# schematic.net
KiCad netlist of a schematic drawn in EasyEDA
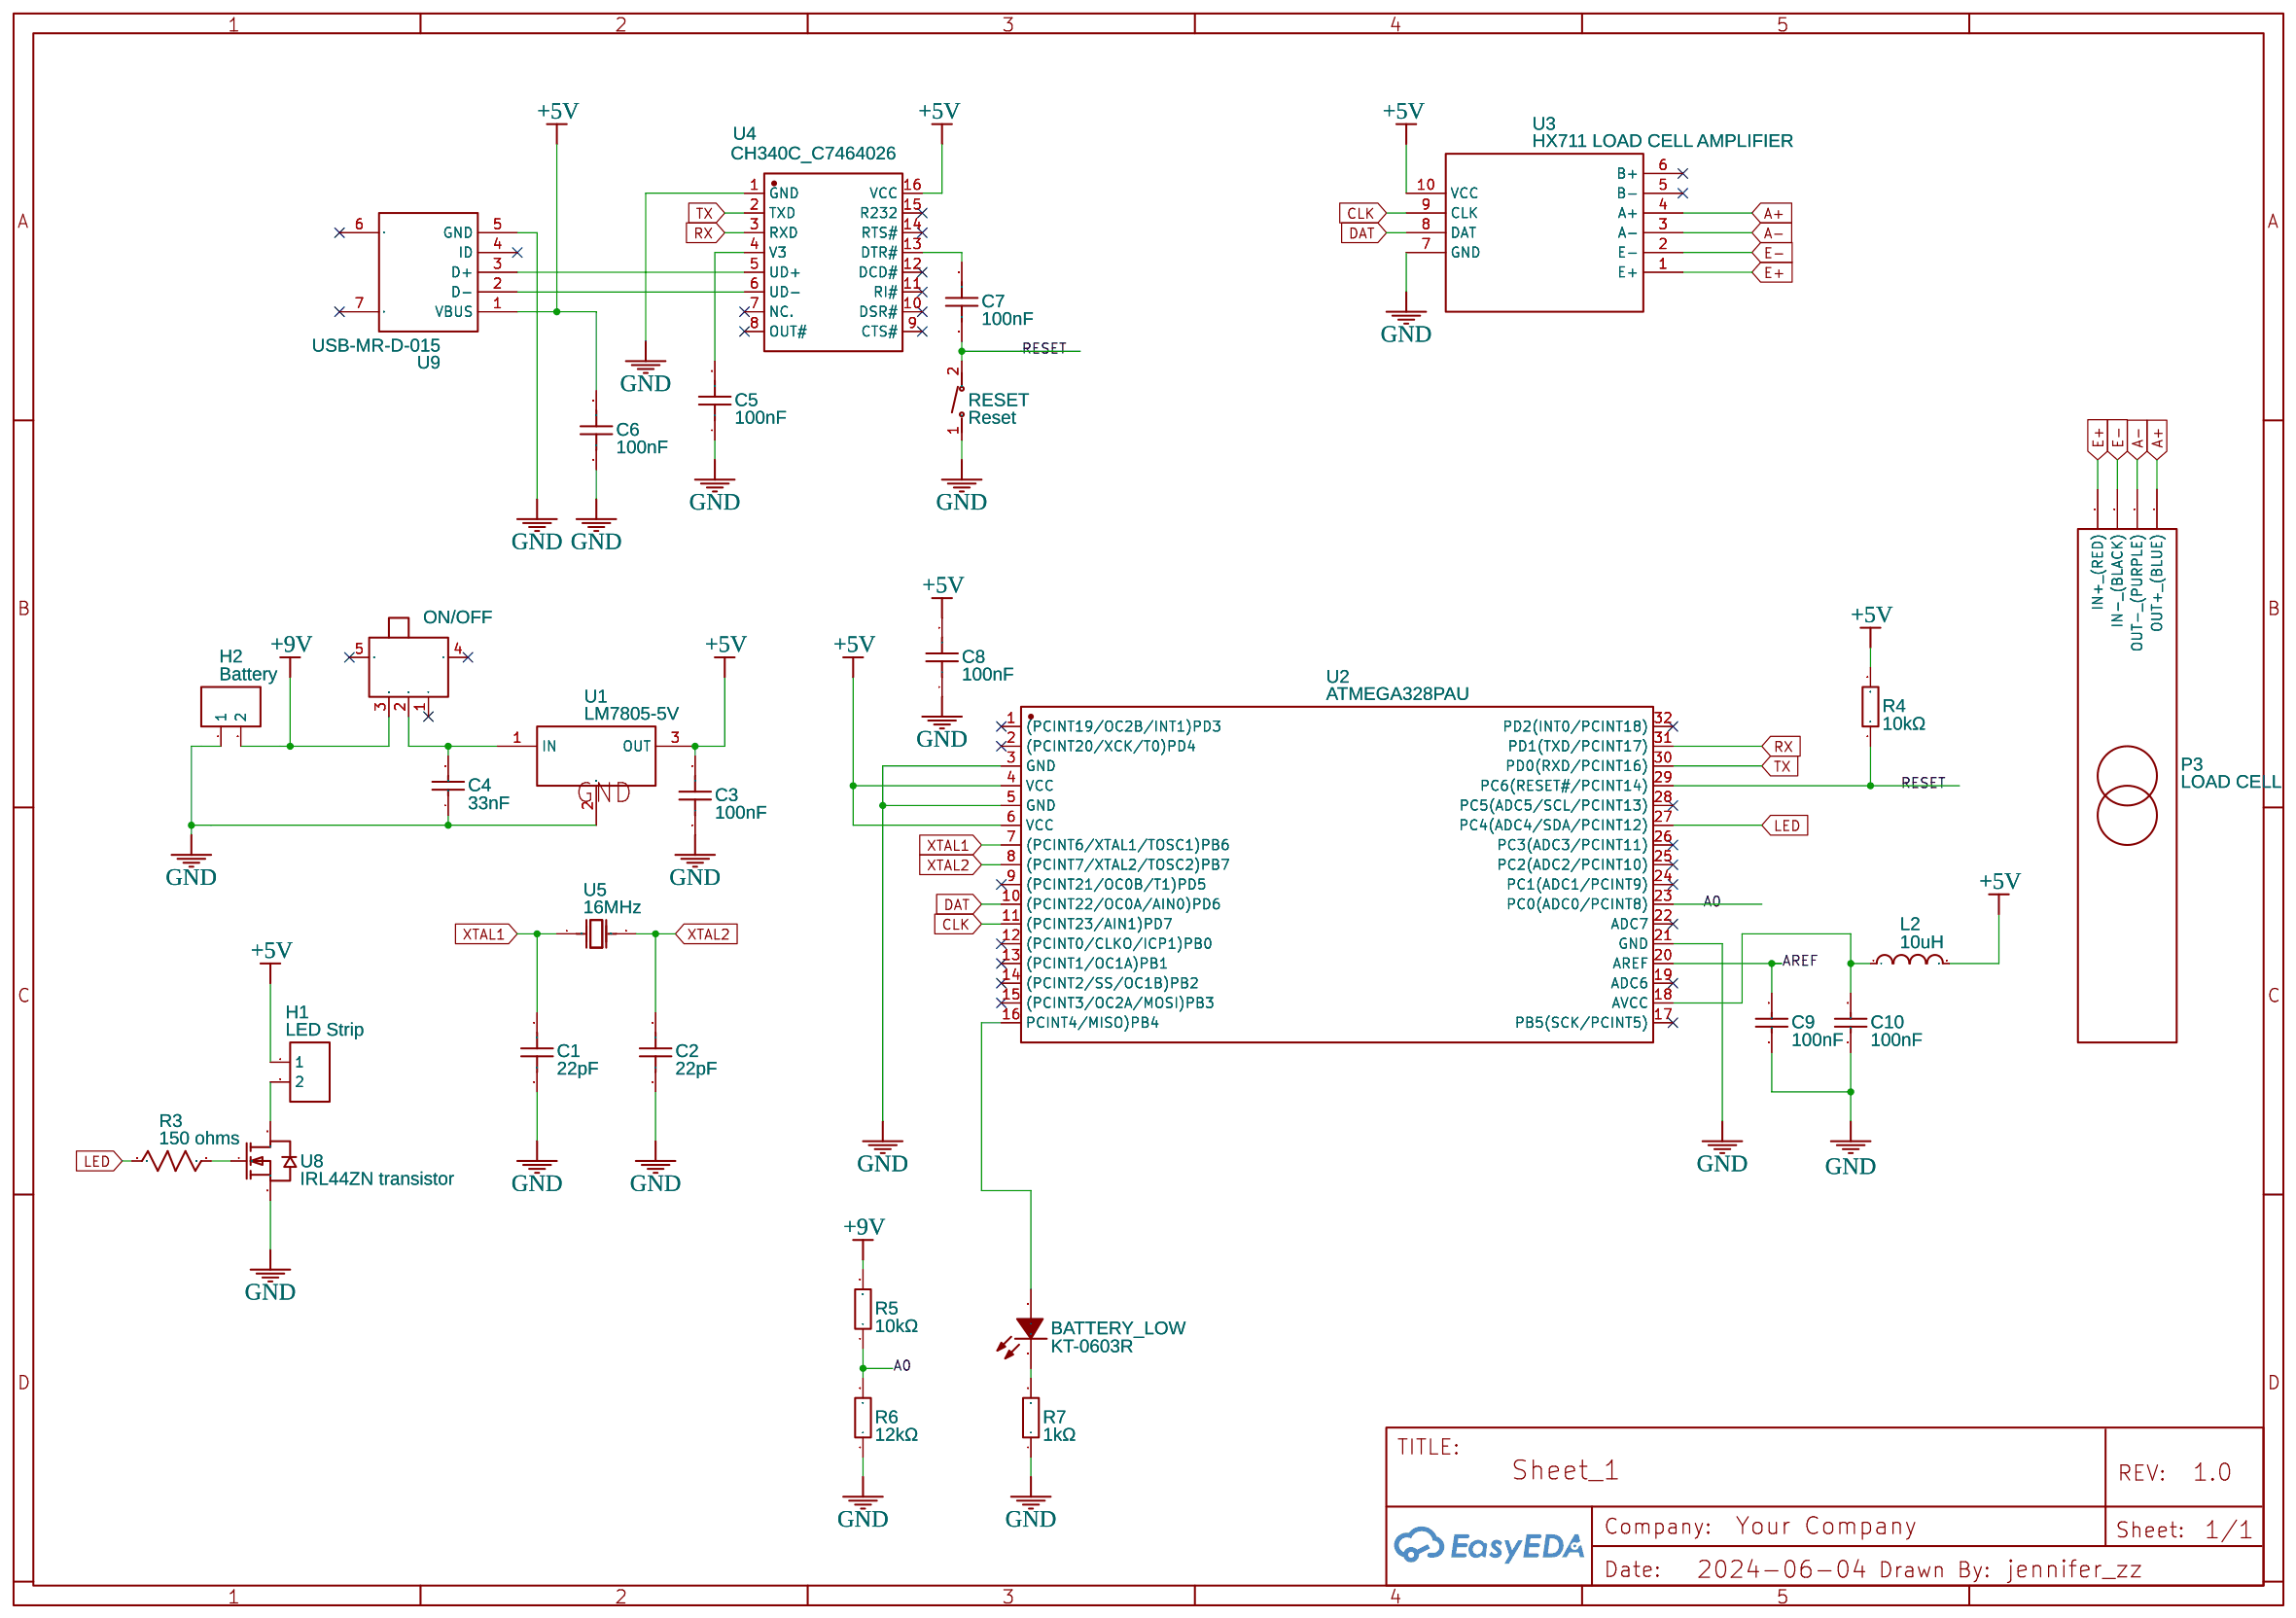
[diagram p0: schematic sheet]

(export (version "E")
  (design (tool "Eeschema 10.0.6"))
  (components
    (comp (ref "BATTERY_LOW")
      (value "KT-0603R")
      (fields (field (name "Manufacturer") "KENTO"))
      (libsource (lib "") (part "KT-0603R"))
    )
    (comp (ref "C1") (value "22pF") (libsource (lib "") (part "C_0603_US")))
    (comp (ref "C2") (value "22pF") (libsource (lib "") (part "C_0603_US")))
    (comp (ref "C3")
      (value "100nF")
      (fields
        (field (name "Manufacturer Part") "CC0603KRX7R9BB104")
        (field (name "Manufacturer") "YAGEO(国巨)")
      )
      (libsource (lib "") (part "CC0603KRX7R9BB104"))
    )
    (comp (ref "C4")
      (value "33nF")
      (fields
        (field (name "Manufacturer Part") "CL10B333KB8NNNC")
        (field (name "Manufacturer") "SAMSUNG(三星)")
      )
      (libsource (lib "") (part "CL10B333KB8NNNC"))
    )
    (comp (ref "C5")
      (value "100nF")
      (fields
        (field (name "Manufacturer Part") "CC0603KRX7R9BB104")
        (field (name "Manufacturer") "YAGEO(国巨)")
      )
      (libsource (lib "") (part "CC0603KRX7R9BB104"))
    )
    (comp (ref "C6")
      (value "100nF")
      (fields
        (field (name "Manufacturer Part") "CC0603KRX7R9BB104")
        (field (name "Manufacturer") "YAGEO(国巨)")
      )
      (libsource (lib "") (part "CC0603KRX7R9BB104"))
    )
    (comp (ref "C7")
      (value "100nF")
      (fields
        (field (name "Manufacturer Part") "CC0603KRX7R9BB104")
        (field (name "Manufacturer") "YAGEO(国巨)")
      )
      (libsource (lib "") (part "CC0603KRX7R9BB104"))
    )
    (comp (ref "C8")
      (value "100nF")
      (fields
        (field (name "Manufacturer Part") "CC0603KRX7R9BB104")
        (field (name "Manufacturer") "YAGEO(国巨)")
      )
      (libsource (lib "") (part "CC0603KRX7R9BB104"))
    )
    (comp (ref "C9")
      (value "100nF")
      (fields
        (field (name "Manufacturer Part") "CL10B104KO8NNNC")
        (field (name "Manufacturer") "SAMSUNG(三星)")
      )
      (libsource (lib "") (part "CL10B104KO8NNNC"))
    )
    (comp (ref "C10")
      (value "100nF")
      (fields
        (field (name "Manufacturer Part") "CL10B104KO8NNNC")
        (field (name "Manufacturer") "SAMSUNG(三星)")
      )
      (libsource (lib "") (part "CL10B104KO8NNNC"))
    )
    (comp (ref "H1") (value "LED Strip") (libsource (lib "") (part "HDR-F-2.54_1x2_1")))
    (comp (ref "H2") (value "Battery") (libsource (lib "") (part "HDR-F-2.54_1x2")))
    (comp (ref "L2")
      (value "10uH")
      (fields (field (name "Manufacturer Part") "CV201210-100K") (field (name "Manufacturer") "BOURNS"))
      (libsource (lib "") (part "CV201210-100K"))
    )
    (comp (ref "ON/OFF")
      (value "switch")
      (fields
        (field (name "Manufacturer Part") "SS12D07VG4 087")
        (field (name "Manufacturer") "SHOU HAN(首韩)")
      )
      (libsource (lib "") (part "SS12D07VG4 087"))
    )
    (comp (ref "P3") (value "LOAD CELL") (libsource (lib "") (part "LOAD CELL")))
    (comp (ref "R3") (value "150 ohms") (libsource (lib "") (part "R_0603_US")))
    (comp (ref "R4")
      (value "10kΩ")
      (fields
        (field (name "Manufacturer Part") "0603WAF1002T5E")
        (field (name "Manufacturer") "UNI-ROYAL(厚声)")
      )
      (libsource (lib "") (part "0603WAF1002T5E"))
    )
    (comp (ref "R5")
      (value "10kΩ")
      (fields
        (field (name "Manufacturer Part") "0603WAF1002T5E")
        (field (name "Manufacturer") "UNI-ROYAL(厚声)")
      )
      (libsource (lib "") (part "0603WAF1002T5E"))
    )
    (comp (ref "R6")
      (value "12kΩ")
      (fields
        (field (name "Manufacturer Part") "QR0603F12K0P05Z")
        (field (name "Manufacturer") "EVER OHMS(天二科技)")
      )
      (libsource (lib "") (part "QR0603F12KP05"))
    )
    (comp (ref "R7")
      (value "1kΩ")
      (fields
        (field (name "Manufacturer Part") "0603WAF1001T5E")
        (field (name "Manufacturer") "UNI-ROYAL(厚声)")
      )
      (libsource (lib "") (part "0603WAF1001T5E"))
    )
    (comp (ref "RESET")
      (value "Reset")
      (fields (field (name "Manufacturer Part") "BUTTON"))
      (libsource (lib "") (part "BUTTON_C9900040040"))
    )
    (comp (ref "U1") (value "LM7805-5V") (libsource (lib "") (part "LM7805-5V")))
    (comp (ref "U2")
      (value "ATMEGA328PAU")
      (fields (field (name "Manufacturer Part") "Atmega328pAU"))
      (libsource (lib "") (part "ATMEGA328PAU"))
    )
    (comp (ref "U3")
      (value "HX711 LOAD CELL AMPLIFIER")
      (libsource (lib "") (part "HX711 LOAD CELL AMPLIFIER"))
    )
    (comp (ref "U4")
      (value "CH340C_C7464026")
      (fields (field (name "Manufacturer Part") "CH340C") (field (name "Manufacturer") "WCH(南京沁恒)"))
      (libsource (lib "") (part "CH340C_C7464026"))
    )
    (comp (ref "U5")
      (value "16MHz")
      (fields (field (name "Manufacturer Part") "D22011000143-Y1"))
      (libsource (lib "") (part "D22011000143-Y1"))
    )
    (comp (ref "U8")
      (value "IRL44ZN transistor")
      (fields (field (name "Manufacturer Part") "si2302-nmosfet"))
      (libsource (lib "") (part "SI2302-NMOSFET"))
    )
    (comp (ref "U9")
      (value "USB-MR-D-015")
      (fields (field (name "Manufacturer") "DEALON(德艺隆)"))
      (libsource (lib "") (part "USB-MR-D-015"))
    )
  )
  (nets
    (net (code "1") (name "+5V") (class "Default")
      (node (ref "C3") (pin "2") (pinfunction "2_2") (pintype "unspecified"))
      (node (ref "C6") (pin "2") (pinfunction "2_2") (pintype "unspecified"))
      (node (ref "C8") (pin "2") (pinfunction "2_2") (pintype "unspecified"))
      (node (ref "H1") (pin "1") (pinfunction "1_1") (pintype "input"))
      (node (ref "L2") (pin "2") (pinfunction "2_2") (pintype "unspecified"))
      (node (ref "R4") (pin "2") (pinfunction "2_2") (pintype "input"))
      (node (ref "U1") (pin "3") (pinfunction "OUT_3") (pintype "passive"))
      (node (ref "U2") (pin "4") (pinfunction "VCC_4") (pintype "unspecified"))
      (node (ref "U2") (pin "6") (pinfunction "VCC_6") (pintype "unspecified"))
      (node (ref "U3") (pin "10") (pinfunction "VCC_10") (pintype "unspecified"))
      (node (ref "U4") (pin "16") (pinfunction "VCC_16") (pintype "unspecified"))
      (node (ref "U9") (pin "1") (pinfunction "VBUS_1") (pintype "unspecified"))
    )
    (net (code "2") (name "+9V") (class "Default")
      (node (ref "H2") (pin "2") (pinfunction "2_2") (pintype "input"))
      (node (ref "ON/OFF") (pin "3") (pinfunction "3_3") (pintype "unspecified"))
      (node (ref "R5") (pin "2") (pinfunction "2_2") (pintype "input"))
    )
    (net (code "3") (name "/A0") (class "Default")
      (node (ref "R5") (pin "1") (pinfunction "1_1") (pintype "input"))
      (node (ref "R6") (pin "2") (pinfunction "2_2") (pintype "unspecified"))
      (node (ref "U2") (pin "23") (pinfunction "PC0(ADC0/PCINT8)_23") (pintype "unspecified"))
    )
    (net (code "4") (name "/AREF") (class "Default")
      (node (ref "C9") (pin "2") (pinfunction "2_2") (pintype "input"))
      (node (ref "U2") (pin "20") (pinfunction "AREF_20") (pintype "unspecified"))
    )
    (net (code "5") (name "/RESET") (class "Default")
      (node (ref "C7") (pin "1") (pinfunction "1_1") (pintype "unspecified"))
      (node (ref "R4") (pin "1") (pinfunction "1_1") (pintype "input"))
      (node (ref "RESET") (pin "2") (pinfunction "B_2") (pintype "unspecified"))
      (node (ref "U2") (pin "29") (pinfunction "PC6(RESET#/PCINT14)_29") (pintype "unspecified"))
    )
    (net (code "6") (name "A+") (class "Default")
      (node (ref "P3") (pin "4") (pinfunction "OUT+_(BLUE)_4") (pintype "unspecified"))
      (node (ref "U3") (pin "4") (pinfunction "A+_4") (pintype "unspecified"))
    )
    (net (code "7") (name "A-") (class "Default")
      (node (ref "P3") (pin "3") (pinfunction "OUT-_(PURPLE)_3") (pintype "unspecified"))
      (node (ref "U3") (pin "3") (pinfunction "A-_3") (pintype "unspecified"))
    )
    (net (code "8") (name "CLK") (class "Default")
      (node (ref "U2") (pin "11") (pinfunction "(PCINT23/AIN1)PD7_11") (pintype "unspecified"))
      (node (ref "U3") (pin "9") (pinfunction "CLK_9") (pintype "unspecified"))
    )
    (net (code "9") (name "DAT") (class "Default")
      (node (ref "U2") (pin "10") (pinfunction "(PCINT22/OC0A/AIN0)PD6_10") (pintype "unspecified"))
      (node (ref "U3") (pin "8") (pinfunction "DAT_8") (pintype "unspecified"))
    )
    (net (code "10") (name "E+") (class "Default")
      (node (ref "P3") (pin "1") (pinfunction "IN+_(RED)_1") (pintype "unspecified"))
      (node (ref "U3") (pin "1") (pinfunction "E+_1") (pintype "unspecified"))
    )
    (net (code "11") (name "E-") (class "Default")
      (node (ref "P3") (pin "2") (pinfunction "IN-_(BLACK)_2") (pintype "unspecified"))
      (node (ref "U3") (pin "2") (pinfunction "E-_2") (pintype "unspecified"))
    )
    (net (code "12") (name "GND") (class "Default")
      (node (ref "C1") (pin "2") (pinfunction "2_2") (pintype "unspecified"))
      (node (ref "C10") (pin "1") (pinfunction "1_1") (pintype "input"))
      (node (ref "C2") (pin "2") (pinfunction "2_2") (pintype "unspecified"))
      (node (ref "C3") (pin "1") (pinfunction "1_1") (pintype "unspecified"))
      (node (ref "C4") (pin "1") (pinfunction "1_1") (pintype "input"))
      (node (ref "C5") (pin "1") (pinfunction "1_1") (pintype "unspecified"))
      (node (ref "C6") (pin "1") (pinfunction "1_1") (pintype "unspecified"))
      (node (ref "C8") (pin "1") (pinfunction "1_1") (pintype "unspecified"))
      (node (ref "C9") (pin "1") (pinfunction "1_1") (pintype "input"))
      (node (ref "H2") (pin "1") (pinfunction "1_1") (pintype "input"))
      (node (ref "R6") (pin "1") (pinfunction "1_1") (pintype "unspecified"))
      (node (ref "R7") (pin "1") (pinfunction "1_1") (pintype "input"))
      (node (ref "RESET") (pin "1") (pinfunction "A_1") (pintype "unspecified"))
      (node (ref "U1") (pin "2") (pinfunction "GND_2") (pintype "passive"))
      (node (ref "U2") (pin "21") (pinfunction "GND_21") (pintype "unspecified"))
      (node (ref "U2") (pin "3") (pinfunction "GND_3") (pintype "unspecified"))
      (node (ref "U2") (pin "5") (pinfunction "GND_5") (pintype "unspecified"))
      (node (ref "U3") (pin "7") (pinfunction "GND_7") (pintype "unspecified"))
      (node (ref "U4") (pin "1") (pinfunction "GND_1") (pintype "unspecified"))
      (node (ref "U8") (pin "2") (pinfunction "S_2") (pintype "unspecified"))
      (node (ref "U9") (pin "5") (pinfunction "GND_5") (pintype "unspecified"))
    )
    (net (code "13") (name "LED") (class "Default")
      (node (ref "R3") (pin "1") (pinfunction "1_1") (pintype "unspecified"))
      (node (ref "U2") (pin "27") (pinfunction "PC4(ADC4/SDA/PCINT12)_27") (pintype "unspecified"))
    )
    (net (code "14") (name "Net-(BATTERY_LOW-A)") (class "Default")
      (node (ref "BATTERY_LOW") (pin "2") (pinfunction "A_2") (pintype "unspecified"))
      (node (ref "U2") (pin "16") (pinfunction "PCINT4/MISO)PB4_16") (pintype "unspecified"))
    )
    (net (code "15") (name "Net-(BATTERY_LOW-K)") (class "Default")
      (node (ref "BATTERY_LOW") (pin "1") (pinfunction "K_1") (pintype "unspecified"))
      (node (ref "R7") (pin "2") (pinfunction "2_2") (pintype "input"))
    )
    (net (code "16") (name "Net-(U1-IN)") (class "Default")
      (node (ref "C4") (pin "2") (pinfunction "2_2") (pintype "input"))
      (node (ref "ON/OFF") (pin "2") (pinfunction "2_2") (pintype "unspecified"))
      (node (ref "U1") (pin "1") (pinfunction "IN_1") (pintype "passive"))
    )
    (net (code "17") (name "Net-(U2-AVCC)") (class "Default")
      (node (ref "C10") (pin "2") (pinfunction "2_2") (pintype "input"))
      (node (ref "L2") (pin "1") (pinfunction "1_1") (pintype "unspecified"))
      (node (ref "U2") (pin "18") (pinfunction "AVCC_18") (pintype "unspecified"))
    )
    (net (code "18") (name "Net-(U4-DTR#)") (class "Default")
      (node (ref "C7") (pin "2") (pinfunction "2_2") (pintype "unspecified"))
      (node (ref "U4") (pin "13") (pinfunction "DTR#_13") (pintype "unspecified"))
    )
    (net (code "19") (name "Net-(U4-UD+)") (class "Default")
      (node (ref "U4") (pin "5") (pinfunction "UD+_5") (pintype "unspecified"))
      (node (ref "U9") (pin "3") (pinfunction "D+_3") (pintype "unspecified"))
    )
    (net (code "20") (name "Net-(U4-UD-)") (class "Default")
      (node (ref "U4") (pin "6") (pinfunction "UD-_6") (pintype "unspecified"))
      (node (ref "U9") (pin "2") (pinfunction "D-_2") (pintype "unspecified"))
    )
    (net (code "21") (name "Net-(U4-V3)") (class "Default")
      (node (ref "C5") (pin "2") (pinfunction "2_2") (pintype "unspecified"))
      (node (ref "U4") (pin "4") (pinfunction "V3_4") (pintype "unspecified"))
    )
    (net (code "22") (name "Net-(U8-D)") (class "Default")
      (node (ref "H1") (pin "2") (pinfunction "2_2") (pintype "input"))
      (node (ref "U8") (pin "3") (pinfunction "D_3") (pintype "unspecified"))
    )
    (net (code "23") (name "Net-(U8-G)") (class "Default")
      (node (ref "R3") (pin "2") (pinfunction "2_2") (pintype "unspecified"))
      (node (ref "U8") (pin "1") (pinfunction "G_1") (pintype "unspecified"))
    )
    (net (code "24") (name "RX") (class "Default")
      (node (ref "U2") (pin "31") (pinfunction "PD1(TXD/PCINT17)_31") (pintype "unspecified"))
      (node (ref "U4") (pin "3") (pinfunction "RXD_3") (pintype "unspecified"))
    )
    (net (code "25") (name "TX") (class "Default")
      (node (ref "U2") (pin "30") (pinfunction "PD0(RXD/PCINT16)_30") (pintype "unspecified"))
      (node (ref "U4") (pin "2") (pinfunction "TXD_2") (pintype "unspecified"))
    )
    (net (code "26") (name "XTAL1") (class "Default")
      (node (ref "C1") (pin "1") (pinfunction "1_1") (pintype "unspecified"))
      (node (ref "U2") (pin "7") (pinfunction "(PCINT6/XTAL1/TOSC1)PB6_7") (pintype "unspecified"))
      (node (ref "U5") (pin "1") (pinfunction "OSC1_1") (pintype "input"))
    )
    (net (code "27") (name "XTAL2") (class "Default")
      (node (ref "C2") (pin "1") (pinfunction "1_1") (pintype "unspecified"))
      (node (ref "U2") (pin "8") (pinfunction "(PCINT7/XTAL2/TOSC2)PB7_8") (pintype "unspecified"))
      (node (ref "U5") (pin "2") (pinfunction "OSC2_2") (pintype "input"))
    )
    (net (code "28") (name "unconnected-(ON/OFF-Pad1)") (class "Default")
      (node (ref "ON/OFF") (pin "1") (pinfunction "1_1") (pintype "unspecified+no_connect"))
    )
    (net (code "29") (name "unconnected-(ON/OFF-Pad4)") (class "Default")
      (node (ref "ON/OFF") (pin "4") (pinfunction "4_4") (pintype "unspecified+no_connect"))
    )
    (net (code "30") (name "unconnected-(ON/OFF-Pad5)") (class "Default")
      (node (ref "ON/OFF") (pin "5") (pinfunction "5_5") (pintype "unspecified+no_connect"))
    )
    (net (code "31") (name "unconnected-(U2-(PCINT0{slash}CLKO{slash}ICP1)PB0-Pad12)") (class "Default")
      (node (ref "U2") (pin "12") (pinfunction "(PCINT0/CLKO/ICP1)PB0_12") (pintype "unspecified+no_connect"))
    )
    (net (code "32") (name "unconnected-(U2-(PCINT1{slash}OC1A)PB1-Pad13)") (class "Default")
      (node (ref "U2") (pin "13") (pinfunction "(PCINT1/OC1A)PB1_13") (pintype "unspecified+no_connect"))
    )
    (net (code "33") (name "unconnected-(U2-(PCINT2{slash}SS{slash}OC1B)PB2-Pad14)") (class "Default")
      (node (ref "U2") (pin "14") (pinfunction "(PCINT2/SS/OC1B)PB2_14") (pintype "unspecified+no_connect"))
    )
    (net (code "34") (name "unconnected-(U2-(PCINT3{slash}OC2A{slash}MOSI)PB3-Pad15)") (class "Default")
      (node (ref "U2") (pin "15") (pinfunction "(PCINT3/OC2A/MOSI)PB3_15") (pintype "unspecified+no_connect"))
    )
    (net (code "35") (name "unconnected-(U2-(PCINT19{slash}OC2B{slash}INT1)PD3-Pad1)") (class "Default")
      (node (ref "U2") (pin "1") (pinfunction "(PCINT19/OC2B/INT1)PD3_1") (pintype "unspecified+no_connect"))
    )
    (net (code "36") (name "unconnected-(U2-(PCINT20{slash}XCK{slash}T0)PD4-Pad2)") (class "Default")
      (node (ref "U2") (pin "2") (pinfunction "(PCINT20/XCK/T0)PD4_2") (pintype "unspecified+no_connect"))
    )
    (net (code "37") (name "unconnected-(U2-(PCINT21{slash}OC0B{slash}T1)PD5-Pad9)") (class "Default")
      (node (ref "U2") (pin "9") (pinfunction "(PCINT21/OC0B/T1)PD5_9") (pintype "unspecified+no_connect"))
    )
    (net (code "38") (name "unconnected-(U2-ADC6-Pad19)") (class "Default")
      (node (ref "U2") (pin "19") (pinfunction "ADC6_19") (pintype "unspecified+no_connect"))
    )
    (net (code "39") (name "unconnected-(U2-ADC7-Pad22)") (class "Default")
      (node (ref "U2") (pin "22") (pinfunction "ADC7_22") (pintype "unspecified+no_connect"))
    )
    (net (code "40") (name "unconnected-(U2-PB5(SCK{slash}PCINT5)-Pad17)") (class "Default")
      (node (ref "U2") (pin "17") (pinfunction "PB5(SCK/PCINT5)_17") (pintype "unspecified+no_connect"))
    )
    (net (code "41") (name "unconnected-(U2-PC1(ADC1{slash}PCINT9)-Pad24)") (class "Default")
      (node (ref "U2") (pin "24") (pinfunction "PC1(ADC1/PCINT9)_24") (pintype "unspecified+no_connect"))
    )
    (net (code "42") (name "unconnected-(U2-PC2(ADC2{slash}PCINT10)-Pad25)") (class "Default")
      (node (ref "U2") (pin "25") (pinfunction "PC2(ADC2/PCINT10)_25") (pintype "unspecified+no_connect"))
    )
    (net (code "43") (name "unconnected-(U2-PC3(ADC3{slash}PCINT11)-Pad26)") (class "Default")
      (node (ref "U2") (pin "26") (pinfunction "PC3(ADC3/PCINT11)_26") (pintype "unspecified+no_connect"))
    )
    (net (code "44") (name "unconnected-(U2-PC5(ADC5{slash}SCL{slash}PCINT13)-Pad28)") (class "Default")
      (node (ref "U2") (pin "28") (pinfunction "PC5(ADC5/SCL/PCINT13)_28") (pintype "unspecified+no_connect"))
    )
    (net (code "45") (name "unconnected-(U2-PD2(INT0{slash}PCINT18)-Pad32)") (class "Default")
      (node (ref "U2") (pin "32") (pinfunction "PD2(INT0/PCINT18)_32") (pintype "unspecified+no_connect"))
    )
    (net (code "46") (name "unconnected-(U3-B+-Pad6)") (class "Default")
      (node (ref "U3") (pin "6") (pinfunction "B+_6") (pintype "unspecified+no_connect"))
    )
    (net (code "47") (name "unconnected-(U3-B--Pad5)") (class "Default")
      (node (ref "U3") (pin "5") (pinfunction "B-_5") (pintype "unspecified+no_connect"))
    )
    (net (code "48") (name "unconnected-(U4-CTS#-Pad9)") (class "Default")
      (node (ref "U4") (pin "9") (pinfunction "CTS#_9") (pintype "unspecified+no_connect"))
    )
    (net (code "49") (name "unconnected-(U4-DCD#-Pad12)") (class "Default")
      (node (ref "U4") (pin "12") (pinfunction "DCD#_12") (pintype "unspecified+no_connect"))
    )
    (net (code "50") (name "unconnected-(U4-DSR#-Pad10)") (class "Default")
      (node (ref "U4") (pin "10") (pinfunction "DSR#_10") (pintype "unspecified+no_connect"))
    )
    (net (code "51") (name "unconnected-(U4-NC.-Pad7)") (class "Default")
      (node (ref "U4") (pin "7") (pinfunction "NC._7") (pintype "unspecified+no_connect"))
    )
    (net (code "52") (name "unconnected-(U4-OUT#-Pad8)") (class "Default")
      (node (ref "U4") (pin "8") (pinfunction "OUT#_8") (pintype "unspecified+no_connect"))
    )
    (net (code "53") (name "unconnected-(U4-R232-Pad15)") (class "Default")
      (node (ref "U4") (pin "15") (pinfunction "R232_15") (pintype "unspecified+no_connect"))
    )
    (net (code "54") (name "unconnected-(U4-RI#-Pad11)") (class "Default")
      (node (ref "U4") (pin "11") (pinfunction "RI#_11") (pintype "unspecified+no_connect"))
    )
    (net (code "55") (name "unconnected-(U4-RTS#-Pad14)") (class "Default")
      (node (ref "U4") (pin "14") (pinfunction "RTS#_14") (pintype "unspecified+no_connect"))
    )
    (net (code "56") (name "unconnected-(U9-EH-Pad6)") (class "Default")
      (node (ref "U9") (pin "6") (pinfunction "EH_6") (pintype "unspecified+no_connect"))
    )
    (net (code "57") (name "unconnected-(U9-EH-Pad7)") (class "Default")
      (node (ref "U9") (pin "7") (pinfunction "EH_7") (pintype "unspecified+no_connect"))
    )
    (net (code "58") (name "unconnected-(U9-ID-Pad4)") (class "Default")
      (node (ref "U9") (pin "4") (pinfunction "ID_4") (pintype "unspecified+no_connect"))
    )
  )
)
